# piano_keys.net
KiCad netlist of a schematic drawn in EAGLE
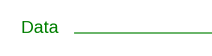
[diagram p0: schematic, sheet 1, part 1 of 2]
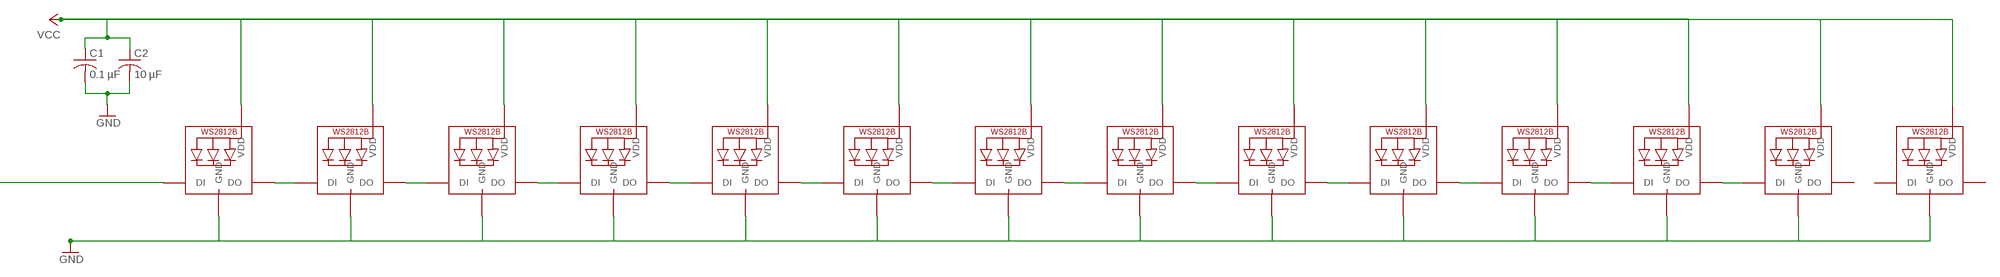
[diagram p1: schematic, sheet 1, part 2 of 2]

(export (version "E")
  (design (tool "Eeschema 10.0.6"))
  (components
    (comp (ref "C1")
      (value "0.1 µF")
      (footprint "eagle-import:C025-024X044")
      (libsource (lib "eagle-import") (part "C-US025-024X044"))
    )
    (comp (ref "C2")
      (value "10 µF")
      (footprint "eagle-import:C025-024X044")
      (libsource (lib "eagle-import") (part "C-US025-024X044"))
    )
    (comp (ref "LED1")
      (value "WS2812B5050")
      (footprint "eagle-import:WS2812B")
      (libsource (lib "eagle-import") (part "WS2812B5050"))
    )
    (comp (ref "LED2")
      (value "WS2812B5050")
      (footprint "eagle-import:WS2812B")
      (libsource (lib "eagle-import") (part "WS2812B5050"))
    )
    (comp (ref "LED3")
      (value "WS2812B5050")
      (footprint "eagle-import:WS2812B")
      (libsource (lib "eagle-import") (part "WS2812B5050"))
    )
    (comp (ref "LED4")
      (value "WS2812B5050")
      (footprint "eagle-import:WS2812B")
      (libsource (lib "eagle-import") (part "WS2812B5050"))
    )
    (comp (ref "LED5")
      (value "WS2812B5050")
      (footprint "eagle-import:WS2812B")
      (libsource (lib "eagle-import") (part "WS2812B5050"))
    )
    (comp (ref "LED6")
      (value "WS2812B5050")
      (footprint "eagle-import:WS2812B")
      (libsource (lib "eagle-import") (part "WS2812B5050"))
    )
    (comp (ref "LED7")
      (value "WS2812B5050")
      (footprint "eagle-import:WS2812B")
      (libsource (lib "eagle-import") (part "WS2812B5050"))
    )
    (comp (ref "LED8")
      (value "WS2812B5050")
      (footprint "eagle-import:WS2812B")
      (libsource (lib "eagle-import") (part "WS2812B5050"))
    )
    (comp (ref "LED9")
      (value "WS2812B5050")
      (footprint "eagle-import:WS2812B")
      (libsource (lib "eagle-import") (part "WS2812B5050"))
    )
    (comp (ref "LED10")
      (value "WS2812B5050")
      (footprint "eagle-import:WS2812B")
      (libsource (lib "eagle-import") (part "WS2812B5050"))
    )
    (comp (ref "LED11")
      (value "WS2812B5050")
      (footprint "eagle-import:WS2812B")
      (libsource (lib "eagle-import") (part "WS2812B5050"))
    )
    (comp (ref "LED12")
      (value "WS2812B5050")
      (footprint "eagle-import:WS2812B")
      (libsource (lib "eagle-import") (part "WS2812B5050"))
    )
    (comp (ref "LED13")
      (value "WS2812B5050")
      (footprint "eagle-import:WS2812B")
      (libsource (lib "eagle-import") (part "WS2812B5050"))
    )
    (comp (ref "LED14")
      (value "WS2812B5050")
      (footprint "eagle-import:WS2812B")
      (libsource (lib "eagle-import") (part "WS2812B5050"))
    )
  )
  (nets
    (net (code "1") (name "GND") (class "Default")
      (node (ref "C1") (pin "2") (pinfunction "2_2") (pintype "passive"))
      (node (ref "C2") (pin "2") (pinfunction "2_2") (pintype "passive"))
      (node (ref "LED1") (pin "3-GND") (pinfunction "GND_3-GND") (pintype "power_in"))
      (node (ref "LED10") (pin "3-GND") (pinfunction "GND_3-GND") (pintype "power_in"))
      (node (ref "LED11") (pin "3-GND") (pinfunction "GND_3-GND") (pintype "power_in"))
      (node (ref "LED12") (pin "3-GND") (pinfunction "GND_3-GND") (pintype "power_in"))
      (node (ref "LED13") (pin "3-GND") (pinfunction "GND_3-GND") (pintype "power_in"))
      (node (ref "LED14") (pin "3-GND") (pinfunction "GND_3-GND") (pintype "power_in"))
      (node (ref "LED2") (pin "3-GND") (pinfunction "GND_3-GND") (pintype "power_in"))
      (node (ref "LED3") (pin "3-GND") (pinfunction "GND_3-GND") (pintype "power_in"))
      (node (ref "LED4") (pin "3-GND") (pinfunction "GND_3-GND") (pintype "power_in"))
      (node (ref "LED5") (pin "3-GND") (pinfunction "GND_3-GND") (pintype "power_in"))
      (node (ref "LED6") (pin "3-GND") (pinfunction "GND_3-GND") (pintype "power_in"))
      (node (ref "LED7") (pin "3-GND") (pinfunction "GND_3-GND") (pintype "power_in"))
      (node (ref "LED8") (pin "3-GND") (pinfunction "GND_3-GND") (pintype "power_in"))
      (node (ref "LED9") (pin "3-GND") (pinfunction "GND_3-GND") (pintype "power_in"))
    )
    (net (code "2") (name "Net-(LED1-DO)") (class "Default")
      (node (ref "LED1") (pin "2-DOUT") (pinfunction "DO_2-DOUT") (pintype "output"))
      (node (ref "LED2") (pin "4-DIN") (pinfunction "DI_4-DIN") (pintype "input"))
    )
    (net (code "3") (name "Net-(LED1-VDD)") (class "Default")
      (node (ref "C1") (pin "1") (pinfunction "1_1") (pintype "passive"))
      (node (ref "C2") (pin "1") (pinfunction "1_1") (pintype "passive"))
      (node (ref "LED1") (pin "1-VDD") (pinfunction "VDD_1-VDD") (pintype "power_in"))
      (node (ref "LED10") (pin "1-VDD") (pinfunction "VDD_1-VDD") (pintype "power_in"))
      (node (ref "LED11") (pin "1-VDD") (pinfunction "VDD_1-VDD") (pintype "power_in"))
      (node (ref "LED12") (pin "1-VDD") (pinfunction "VDD_1-VDD") (pintype "power_in"))
      (node (ref "LED14") (pin "1-VDD") (pinfunction "VDD_1-VDD") (pintype "power_in"))
      (node (ref "LED2") (pin "1-VDD") (pinfunction "VDD_1-VDD") (pintype "power_in"))
      (node (ref "LED3") (pin "1-VDD") (pinfunction "VDD_1-VDD") (pintype "power_in"))
      (node (ref "LED4") (pin "1-VDD") (pinfunction "VDD_1-VDD") (pintype "power_in"))
      (node (ref "LED5") (pin "1-VDD") (pinfunction "VDD_1-VDD") (pintype "power_in"))
      (node (ref "LED6") (pin "1-VDD") (pinfunction "VDD_1-VDD") (pintype "power_in"))
      (node (ref "LED7") (pin "1-VDD") (pinfunction "VDD_1-VDD") (pintype "power_in"))
      (node (ref "LED8") (pin "1-VDD") (pinfunction "VDD_1-VDD") (pintype "power_in"))
      (node (ref "LED9") (pin "1-VDD") (pinfunction "VDD_1-VDD") (pintype "power_in"))
    )
    (net (code "4") (name "Net-(LED2-DO)") (class "Default")
      (node (ref "LED2") (pin "2-DOUT") (pinfunction "DO_2-DOUT") (pintype "output"))
      (node (ref "LED3") (pin "4-DIN") (pinfunction "DI_4-DIN") (pintype "input"))
    )
    (net (code "5") (name "Net-(LED3-DO)") (class "Default")
      (node (ref "LED3") (pin "2-DOUT") (pinfunction "DO_2-DOUT") (pintype "output"))
      (node (ref "LED4") (pin "4-DIN") (pinfunction "DI_4-DIN") (pintype "input"))
    )
    (net (code "6") (name "Net-(LED4-DO)") (class "Default")
      (node (ref "LED4") (pin "2-DOUT") (pinfunction "DO_2-DOUT") (pintype "output"))
      (node (ref "LED5") (pin "4-DIN") (pinfunction "DI_4-DIN") (pintype "input"))
    )
    (net (code "7") (name "Net-(LED5-DO)") (class "Default")
      (node (ref "LED5") (pin "2-DOUT") (pinfunction "DO_2-DOUT") (pintype "output"))
      (node (ref "LED6") (pin "4-DIN") (pinfunction "DI_4-DIN") (pintype "input"))
    )
    (net (code "8") (name "Net-(LED6-DO)") (class "Default")
      (node (ref "LED6") (pin "2-DOUT") (pinfunction "DO_2-DOUT") (pintype "output"))
      (node (ref "LED7") (pin "4-DIN") (pinfunction "DI_4-DIN") (pintype "input"))
    )
    (net (code "9") (name "Net-(LED7-DO)") (class "Default")
      (node (ref "LED7") (pin "2-DOUT") (pinfunction "DO_2-DOUT") (pintype "output"))
      (node (ref "LED8") (pin "4-DIN") (pinfunction "DI_4-DIN") (pintype "input"))
    )
    (net (code "10") (name "Net-(LED8-DO)") (class "Default")
      (node (ref "LED8") (pin "2-DOUT") (pinfunction "DO_2-DOUT") (pintype "output"))
      (node (ref "LED9") (pin "4-DIN") (pinfunction "DI_4-DIN") (pintype "input"))
    )
    (net (code "11") (name "Net-(LED10-DI)") (class "Default")
      (node (ref "LED10") (pin "4-DIN") (pinfunction "DI_4-DIN") (pintype "input"))
      (node (ref "LED9") (pin "2-DOUT") (pinfunction "DO_2-DOUT") (pintype "output"))
    )
    (net (code "12") (name "Net-(LED10-DO)") (class "Default")
      (node (ref "LED10") (pin "2-DOUT") (pinfunction "DO_2-DOUT") (pintype "output"))
      (node (ref "LED11") (pin "4-DIN") (pinfunction "DI_4-DIN") (pintype "input"))
    )
    (net (code "13") (name "Net-(LED11-DO)") (class "Default")
      (node (ref "LED11") (pin "2-DOUT") (pinfunction "DO_2-DOUT") (pintype "output"))
      (node (ref "LED12") (pin "4-DIN") (pinfunction "DI_4-DIN") (pintype "input"))
    )
    (net (code "14") (name "Net-(LED12-DO)") (class "Default")
      (node (ref "LED12") (pin "2-DOUT") (pinfunction "DO_2-DOUT") (pintype "output"))
      (node (ref "LED13") (pin "4-DIN") (pinfunction "DI_4-DIN") (pintype "input"))
    )
    (net (code "16") (name "unconnected-(LED1-DI-Pad4-DIN)") (class "Default")
      (node (ref "LED1") (pin "4-DIN") (pinfunction "DI_4-DIN") (pintype "input"))
    )
    (net (code "17") (name "unconnected-(LED13-DO-Pad2-DOUT)") (class "Default")
      (node (ref "LED13") (pin "2-DOUT") (pinfunction "DO_2-DOUT") (pintype "output"))
    )
    (net (code "18") (name "unconnected-(LED13-VDD-Pad1-VDD)") (class "Default")
      (node (ref "LED13") (pin "1-VDD") (pinfunction "VDD_1-VDD") (pintype "power_in"))
    )
    (net (code "19") (name "unconnected-(LED14-DI-Pad4-DIN)") (class "Default")
      (node (ref "LED14") (pin "4-DIN") (pinfunction "DI_4-DIN") (pintype "input"))
    )
    (net (code "20") (name "unconnected-(LED14-DO-Pad2-DOUT)") (class "Default")
      (node (ref "LED14") (pin "2-DOUT") (pinfunction "DO_2-DOUT") (pintype "output"))
    )
  )
)
